# 7segement4digits1badidea-shield-mk-1.net
KiCad netlist of a schematic drawn in EAGLE
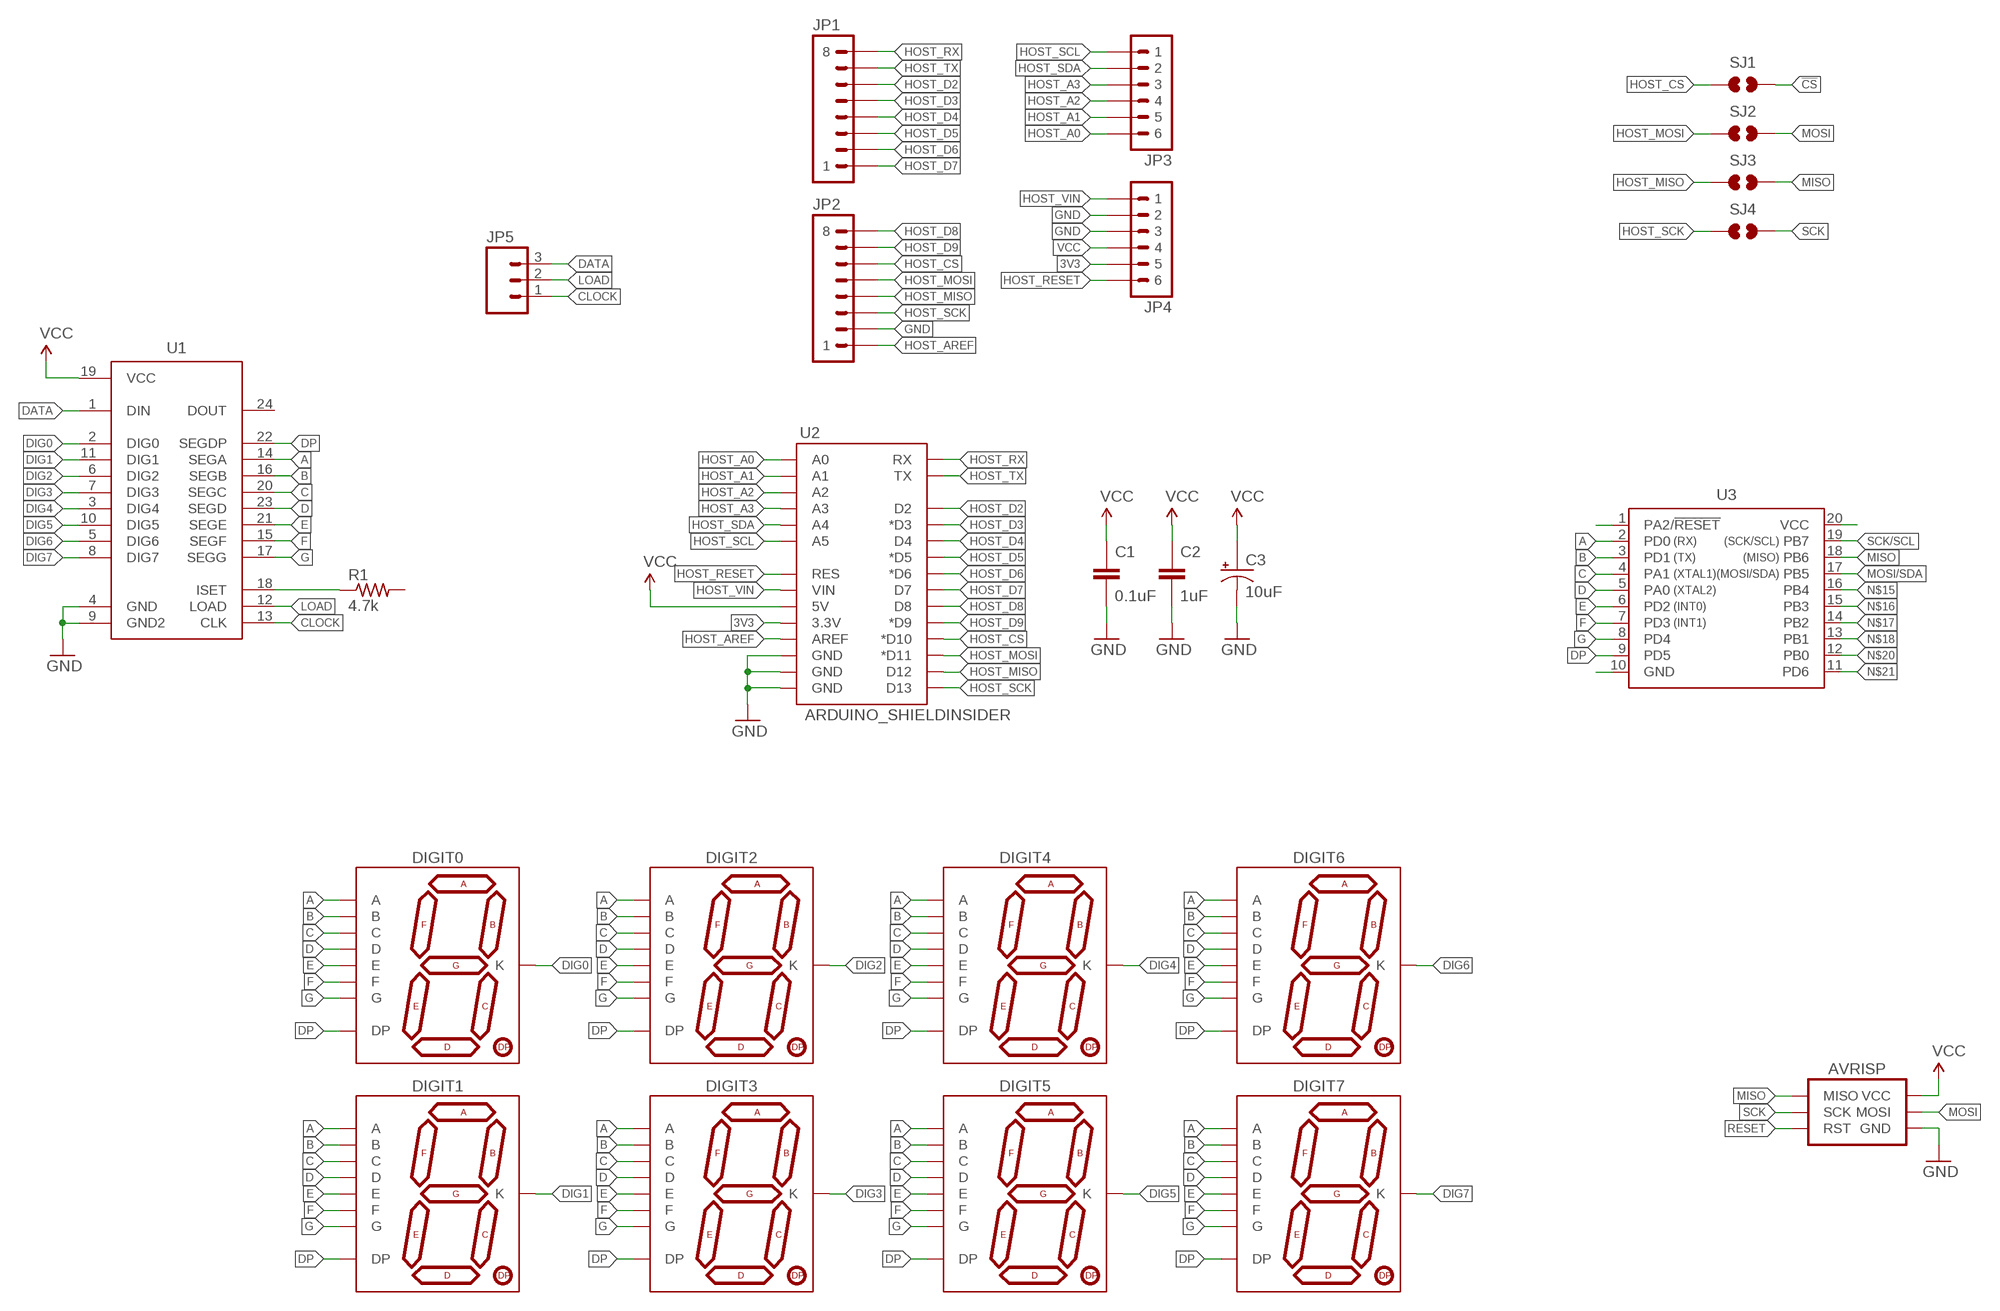
[diagram p0: schematic, sheet 1]

(export (version "E")
  (design (tool "Eeschema 10.0.6"))
  (components
    (comp (ref "AVRISP")
      (value "AVR_SPI_PRG_6PTH")
      (footprint "eagle-import:2X3")
      (libsource (lib "eagle-import") (part "AVR_SPI_PRG_6PTH"))
    )
    (comp (ref "C1")
      (value "0.1uF")
      (footprint "eagle-import:C025-024X044")
      (libsource (lib "eagle-import") (part "CAPACITOR-CERAMIC025-024X044"))
    )
    (comp (ref "C2")
      (value "1uF")
      (footprint "eagle-import:C025-024X044")
      (libsource (lib "eagle-import") (part "CAPACITOR-CERAMIC025-024X044"))
    )
    (comp (ref "C3")
      (value "10uF")
      (footprint "eagle-import:E2,5-5")
      (libsource (lib "eagle-import") (part "CAPACITOR-POLARIZEDE2.5-5"))
    )
    (comp (ref "DIGIT0")
      (value "7SEG_1DIGPTH-10MM")
      (footprint "eagle-import:7SEG_1DIG_10MM")
      (libsource (lib "eagle-import") (part "7SEG_1DIGPTH-10MM"))
    )
    (comp (ref "DIGIT1")
      (value "7SEG_1DIGPTH-10MM")
      (footprint "eagle-import:7SEG_1DIG_10MM")
      (libsource (lib "eagle-import") (part "7SEG_1DIGPTH-10MM"))
    )
    (comp (ref "DIGIT2")
      (value "7SEG_1DIGPTH-10MM")
      (footprint "eagle-import:7SEG_1DIG_10MM")
      (libsource (lib "eagle-import") (part "7SEG_1DIGPTH-10MM"))
    )
    (comp (ref "DIGIT3")
      (value "7SEG_1DIGPTH-10MM")
      (footprint "eagle-import:7SEG_1DIG_10MM")
      (libsource (lib "eagle-import") (part "7SEG_1DIGPTH-10MM"))
    )
    (comp (ref "DIGIT4")
      (value "7SEG_1DIGPTH-10MM")
      (footprint "eagle-import:7SEG_1DIG_10MM")
      (libsource (lib "eagle-import") (part "7SEG_1DIGPTH-10MM"))
    )
    (comp (ref "DIGIT5")
      (value "7SEG_1DIGPTH-10MM")
      (footprint "eagle-import:7SEG_1DIG_10MM")
      (libsource (lib "eagle-import") (part "7SEG_1DIGPTH-10MM"))
    )
    (comp (ref "DIGIT6")
      (value "7SEG_1DIGPTH-10MM")
      (footprint "eagle-import:7SEG_1DIG_10MM")
      (libsource (lib "eagle-import") (part "7SEG_1DIGPTH-10MM"))
    )
    (comp (ref "DIGIT7")
      (value "7SEG_1DIGPTH-10MM")
      (footprint "eagle-import:7SEG_1DIG_10MM")
      (libsource (lib "eagle-import") (part "7SEG_1DIGPTH-10MM"))
    )
    (comp (ref "JP1")
      (value "M081X08")
      (footprint "eagle-import:1X08")
      (libsource (lib "eagle-import") (part "M081X08"))
    )
    (comp (ref "JP2")
      (value "M081X08")
      (footprint "eagle-import:1X08")
      (libsource (lib "eagle-import") (part "M081X08"))
    )
    (comp (ref "JP3")
      (value "M06-NOBS-PTH")
      (footprint "eagle-import:1X06_NOLOCK_FUCKITALL")
      (libsource (lib "eagle-import") (part "M06-NOBS-PTH"))
    )
    (comp (ref "JP4")
      (value "M06-NOBS-PTH")
      (footprint "eagle-import:1X06_NOLOCK_FUCKITALL")
      (libsource (lib "eagle-import") (part "M06-NOBS-PTH"))
    )
    (comp (ref "JP5")
      (value "M03PTH")
      (footprint "eagle-import:1X03")
      (libsource (lib "eagle-import") (part "M03PTH"))
    )
    (comp (ref "R1")
      (value "4.7k")
      (footprint "eagle-import:RESISTOR-AXIAL-PTH-6.35MM")
      (libsource (lib "eagle-import") (part "RESISTORPTH-AXIAL-6.35MM"))
    )
    (comp (ref "SJ1")
      (value "JUMPER-PAD-2-NOYES_SILK")
      (footprint "eagle-import:PAD-JUMPER-2-NO_YES_SILK")
      (libsource (lib "eagle-import") (part "JUMPER-PAD-2-NOYES_SILK"))
    )
    (comp (ref "SJ2")
      (value "JUMPER-PAD-2-NOYES_SILK")
      (footprint "eagle-import:PAD-JUMPER-2-NO_YES_SILK")
      (libsource (lib "eagle-import") (part "JUMPER-PAD-2-NOYES_SILK"))
    )
    (comp (ref "SJ3")
      (value "JUMPER-PAD-2-NOYES_SILK")
      (footprint "eagle-import:PAD-JUMPER-2-NO_YES_SILK")
      (libsource (lib "eagle-import") (part "JUMPER-PAD-2-NOYES_SILK"))
    )
    (comp (ref "SJ4")
      (value "JUMPER-PAD-2-NOYES_SILK")
      (footprint "eagle-import:PAD-JUMPER-2-NO_YES_SILK")
      (libsource (lib "eagle-import") (part "JUMPER-PAD-2-NOYES_SILK"))
    )
    (comp (ref "U1")
      (value "MAX7219DIP")
      (footprint "eagle-import:DIL24")
      (libsource (lib "eagle-import") (part "MAX7219DIP"))
    )
    (comp (ref "U2")
      (value "ARDUINO_SHIELDINSIDER")
      (footprint "eagle-import:ARDUINO_SHIELD_NOOUTLINE_INSIDE")
      (libsource (lib "eagle-import") (part "ARDUINO_SHIELDINSIDER"))
    )
    (comp (ref "U3")
      (value "ATTINY2313ADIP")
      (footprint "eagle-import:DIL20")
      (libsource (lib "eagle-import") (part "ATTINY2313ADIP"))
    )
  )
  (nets
    (net (code "1") (name "/~{CS}") (class "Default")
      (node (ref "SJ1") (pin "2") (pinfunction "2_2") (pintype "passive"))
    )
    (net (code "2") (name "3V3") (class "Default")
      (node (ref "JP4") (pin "5") (pinfunction "5_5") (pintype "passive"))
      (node (ref "U2") (pin "3.3V") (pinfunction "3.3V_3.3V") (pintype "bidirectional"))
    )
    (net (code "3") (name "A") (class "Default")
      (node (ref "DIGIT0") (pin "10") (pinfunction "A_10") (pintype "bidirectional"))
      (node (ref "DIGIT1") (pin "10") (pinfunction "A_10") (pintype "bidirectional"))
      (node (ref "DIGIT2") (pin "10") (pinfunction "A_10") (pintype "bidirectional"))
      (node (ref "DIGIT3") (pin "10") (pinfunction "A_10") (pintype "bidirectional"))
      (node (ref "DIGIT4") (pin "10") (pinfunction "A_10") (pintype "bidirectional"))
      (node (ref "DIGIT5") (pin "10") (pinfunction "A_10") (pintype "bidirectional"))
      (node (ref "DIGIT6") (pin "10") (pinfunction "A_10") (pintype "bidirectional"))
      (node (ref "DIGIT7") (pin "10") (pinfunction "A_10") (pintype "bidirectional"))
      (node (ref "U1") (pin "14") (pinfunction "SEGA_14") (pintype "bidirectional"))
      (node (ref "U3") (pin "2") (pinfunction "PD0_2") (pintype "bidirectional"))
    )
    (net (code "4") (name "B") (class "Default")
      (node (ref "DIGIT0") (pin "9") (pinfunction "B_9") (pintype "bidirectional"))
      (node (ref "DIGIT1") (pin "9") (pinfunction "B_9") (pintype "bidirectional"))
      (node (ref "DIGIT2") (pin "9") (pinfunction "B_9") (pintype "bidirectional"))
      (node (ref "DIGIT3") (pin "9") (pinfunction "B_9") (pintype "bidirectional"))
      (node (ref "DIGIT4") (pin "9") (pinfunction "B_9") (pintype "bidirectional"))
      (node (ref "DIGIT5") (pin "9") (pinfunction "B_9") (pintype "bidirectional"))
      (node (ref "DIGIT6") (pin "9") (pinfunction "B_9") (pintype "bidirectional"))
      (node (ref "DIGIT7") (pin "9") (pinfunction "B_9") (pintype "bidirectional"))
      (node (ref "U1") (pin "16") (pinfunction "SEGB_16") (pintype "bidirectional"))
      (node (ref "U3") (pin "3") (pinfunction "PD1_3") (pintype "bidirectional"))
    )
    (net (code "5") (name "C") (class "Default")
      (node (ref "DIGIT0") (pin "8") (pinfunction "C_8") (pintype "bidirectional"))
      (node (ref "DIGIT1") (pin "8") (pinfunction "C_8") (pintype "bidirectional"))
      (node (ref "DIGIT2") (pin "8") (pinfunction "C_8") (pintype "bidirectional"))
      (node (ref "DIGIT3") (pin "8") (pinfunction "C_8") (pintype "bidirectional"))
      (node (ref "DIGIT4") (pin "8") (pinfunction "C_8") (pintype "bidirectional"))
      (node (ref "DIGIT5") (pin "8") (pinfunction "C_8") (pintype "bidirectional"))
      (node (ref "DIGIT6") (pin "8") (pinfunction "C_8") (pintype "bidirectional"))
      (node (ref "DIGIT7") (pin "8") (pinfunction "C_8") (pintype "bidirectional"))
      (node (ref "U1") (pin "20") (pinfunction "SEGC_20") (pintype "bidirectional"))
      (node (ref "U3") (pin "4") (pinfunction "PA1_4") (pintype "bidirectional"))
    )
    (net (code "6") (name "CLOCK") (class "Default")
      (node (ref "JP5") (pin "1") (pinfunction "1_1") (pintype "passive"))
      (node (ref "U1") (pin "13") (pinfunction "CLK_13") (pintype "bidirectional"))
    )
    (net (code "7") (name "D") (class "Default")
      (node (ref "DIGIT0") (pin "5") (pinfunction "D_5") (pintype "bidirectional"))
      (node (ref "DIGIT1") (pin "5") (pinfunction "D_5") (pintype "bidirectional"))
      (node (ref "DIGIT2") (pin "5") (pinfunction "D_5") (pintype "bidirectional"))
      (node (ref "DIGIT3") (pin "5") (pinfunction "D_5") (pintype "bidirectional"))
      (node (ref "DIGIT4") (pin "5") (pinfunction "D_5") (pintype "bidirectional"))
      (node (ref "DIGIT5") (pin "5") (pinfunction "D_5") (pintype "bidirectional"))
      (node (ref "DIGIT6") (pin "5") (pinfunction "D_5") (pintype "bidirectional"))
      (node (ref "DIGIT7") (pin "5") (pinfunction "D_5") (pintype "bidirectional"))
      (node (ref "U1") (pin "23") (pinfunction "SEGD_23") (pintype "bidirectional"))
      (node (ref "U3") (pin "5") (pinfunction "PA0_5") (pintype "bidirectional"))
    )
    (net (code "8") (name "DATA") (class "Default")
      (node (ref "JP5") (pin "3") (pinfunction "3_3") (pintype "passive"))
      (node (ref "U1") (pin "1") (pinfunction "DIN_1") (pintype "bidirectional"))
    )
    (net (code "9") (name "DIG0") (class "Default")
      (node (ref "DIGIT0") (pin "1") (pinfunction "K_1") (pintype "bidirectional"))
      (node (ref "DIGIT0") (pin "6") (pinfunction "K_6") (pintype "bidirectional"))
      (node (ref "U1") (pin "2") (pinfunction "DIG0_2") (pintype "bidirectional"))
    )
    (net (code "10") (name "DIG1") (class "Default")
      (node (ref "DIGIT1") (pin "1") (pinfunction "K_1") (pintype "bidirectional"))
      (node (ref "DIGIT1") (pin "6") (pinfunction "K_6") (pintype "bidirectional"))
      (node (ref "U1") (pin "11") (pinfunction "DIG1_11") (pintype "bidirectional"))
    )
    (net (code "11") (name "DIG2") (class "Default")
      (node (ref "DIGIT2") (pin "1") (pinfunction "K_1") (pintype "bidirectional"))
      (node (ref "DIGIT2") (pin "6") (pinfunction "K_6") (pintype "bidirectional"))
      (node (ref "U1") (pin "6") (pinfunction "DIG2_6") (pintype "bidirectional"))
    )
    (net (code "12") (name "DIG3") (class "Default")
      (node (ref "DIGIT3") (pin "1") (pinfunction "K_1") (pintype "bidirectional"))
      (node (ref "DIGIT3") (pin "6") (pinfunction "K_6") (pintype "bidirectional"))
      (node (ref "U1") (pin "7") (pinfunction "DIG3_7") (pintype "bidirectional"))
    )
    (net (code "13") (name "DIG4") (class "Default")
      (node (ref "DIGIT4") (pin "1") (pinfunction "K_1") (pintype "bidirectional"))
      (node (ref "DIGIT4") (pin "6") (pinfunction "K_6") (pintype "bidirectional"))
      (node (ref "U1") (pin "3") (pinfunction "DIG4_3") (pintype "bidirectional"))
    )
    (net (code "14") (name "DIG5") (class "Default")
      (node (ref "DIGIT5") (pin "1") (pinfunction "K_1") (pintype "bidirectional"))
      (node (ref "DIGIT5") (pin "6") (pinfunction "K_6") (pintype "bidirectional"))
      (node (ref "U1") (pin "10") (pinfunction "DIG5_10") (pintype "bidirectional"))
    )
    (net (code "15") (name "DIG6") (class "Default")
      (node (ref "DIGIT6") (pin "1") (pinfunction "K_1") (pintype "bidirectional"))
      (node (ref "DIGIT6") (pin "6") (pinfunction "K_6") (pintype "bidirectional"))
      (node (ref "U1") (pin "5") (pinfunction "DIG6_5") (pintype "bidirectional"))
    )
    (net (code "16") (name "DIG7") (class "Default")
      (node (ref "DIGIT7") (pin "1") (pinfunction "K_1") (pintype "bidirectional"))
      (node (ref "DIGIT7") (pin "6") (pinfunction "K_6") (pintype "bidirectional"))
      (node (ref "U1") (pin "8") (pinfunction "DIG7_8") (pintype "bidirectional"))
    )
    (net (code "17") (name "DP") (class "Default")
      (node (ref "DIGIT0") (pin "7") (pinfunction "DP_7") (pintype "bidirectional"))
      (node (ref "DIGIT1") (pin "7") (pinfunction "DP_7") (pintype "bidirectional"))
      (node (ref "DIGIT2") (pin "7") (pinfunction "DP_7") (pintype "bidirectional"))
      (node (ref "DIGIT3") (pin "7") (pinfunction "DP_7") (pintype "bidirectional"))
      (node (ref "DIGIT4") (pin "7") (pinfunction "DP_7") (pintype "bidirectional"))
      (node (ref "DIGIT5") (pin "7") (pinfunction "DP_7") (pintype "bidirectional"))
      (node (ref "DIGIT6") (pin "7") (pinfunction "DP_7") (pintype "bidirectional"))
      (node (ref "DIGIT7") (pin "7") (pinfunction "DP_7") (pintype "bidirectional"))
      (node (ref "U1") (pin "22") (pinfunction "SEGDP_22") (pintype "bidirectional"))
      (node (ref "U3") (pin "9") (pinfunction "PD5_9") (pintype "bidirectional"))
    )
    (net (code "18") (name "E") (class "Default")
      (node (ref "DIGIT0") (pin "4") (pinfunction "E_4") (pintype "bidirectional"))
      (node (ref "DIGIT1") (pin "4") (pinfunction "E_4") (pintype "bidirectional"))
      (node (ref "DIGIT2") (pin "4") (pinfunction "E_4") (pintype "bidirectional"))
      (node (ref "DIGIT3") (pin "4") (pinfunction "E_4") (pintype "bidirectional"))
      (node (ref "DIGIT4") (pin "4") (pinfunction "E_4") (pintype "bidirectional"))
      (node (ref "DIGIT5") (pin "4") (pinfunction "E_4") (pintype "bidirectional"))
      (node (ref "DIGIT6") (pin "4") (pinfunction "E_4") (pintype "bidirectional"))
      (node (ref "DIGIT7") (pin "4") (pinfunction "E_4") (pintype "bidirectional"))
      (node (ref "U1") (pin "21") (pinfunction "SEGE_21") (pintype "bidirectional"))
      (node (ref "U3") (pin "6") (pinfunction "PD2_6") (pintype "bidirectional"))
    )
    (net (code "19") (name "F") (class "Default")
      (node (ref "DIGIT0") (pin "2") (pinfunction "F_2") (pintype "bidirectional"))
      (node (ref "DIGIT1") (pin "2") (pinfunction "F_2") (pintype "bidirectional"))
      (node (ref "DIGIT2") (pin "2") (pinfunction "F_2") (pintype "bidirectional"))
      (node (ref "DIGIT3") (pin "2") (pinfunction "F_2") (pintype "bidirectional"))
      (node (ref "DIGIT4") (pin "2") (pinfunction "F_2") (pintype "bidirectional"))
      (node (ref "DIGIT5") (pin "2") (pinfunction "F_2") (pintype "bidirectional"))
      (node (ref "DIGIT6") (pin "2") (pinfunction "F_2") (pintype "bidirectional"))
      (node (ref "DIGIT7") (pin "2") (pinfunction "F_2") (pintype "bidirectional"))
      (node (ref "U1") (pin "15") (pinfunction "SEGF_15") (pintype "bidirectional"))
      (node (ref "U3") (pin "7") (pinfunction "PD3_7") (pintype "bidirectional"))
    )
    (net (code "20") (name "G") (class "Default")
      (node (ref "DIGIT0") (pin "3") (pinfunction "G_3") (pintype "bidirectional"))
      (node (ref "DIGIT1") (pin "3") (pinfunction "G_3") (pintype "bidirectional"))
      (node (ref "DIGIT2") (pin "3") (pinfunction "G_3") (pintype "bidirectional"))
      (node (ref "DIGIT3") (pin "3") (pinfunction "G_3") (pintype "bidirectional"))
      (node (ref "DIGIT4") (pin "3") (pinfunction "G_3") (pintype "bidirectional"))
      (node (ref "DIGIT5") (pin "3") (pinfunction "G_3") (pintype "bidirectional"))
      (node (ref "DIGIT6") (pin "3") (pinfunction "G_3") (pintype "bidirectional"))
      (node (ref "DIGIT7") (pin "3") (pinfunction "G_3") (pintype "bidirectional"))
      (node (ref "U1") (pin "17") (pinfunction "SEGG_17") (pintype "bidirectional"))
      (node (ref "U3") (pin "8") (pinfunction "PD4_8") (pintype "bidirectional"))
    )
    (net (code "21") (name "GND") (class "Default")
      (node (ref "AVRISP") (pin "6") (pinfunction "GND_6") (pintype "passive"))
      (node (ref "C1") (pin "2") (pinfunction "2_2") (pintype "passive"))
      (node (ref "C2") (pin "2") (pinfunction "2_2") (pintype "passive"))
      (node (ref "C3") (pin "-") (pinfunction "-_-") (pintype "passive"))
      (node (ref "JP2") (pin "2") (pinfunction "2_2") (pintype "passive"))
      (node (ref "JP4") (pin "2") (pinfunction "2_2") (pintype "passive"))
      (node (ref "JP4") (pin "3") (pinfunction "3_3") (pintype "passive"))
      (node (ref "U1") (pin "4") (pinfunction "GND_4") (pintype "bidirectional"))
      (node (ref "U1") (pin "9") (pinfunction "GND2_9") (pintype "bidirectional"))
      (node (ref "U2") (pin "GND@0") (pinfunction "GND_GND@0") (pintype "bidirectional"))
      (node (ref "U2") (pin "GND@1") (pinfunction "GND_GND@1") (pintype "bidirectional"))
      (node (ref "U2") (pin "GND@2") (pinfunction "GND_GND@2") (pintype "bidirectional"))
    )
    (net (code "22") (name "HOST_A0") (class "Default")
      (node (ref "JP3") (pin "6") (pinfunction "6_6") (pintype "passive"))
      (node (ref "U2") (pin "A0") (pinfunction "A0_A0") (pintype "bidirectional"))
    )
    (net (code "23") (name "HOST_A1") (class "Default")
      (node (ref "JP3") (pin "5") (pinfunction "5_5") (pintype "passive"))
      (node (ref "U2") (pin "A1") (pinfunction "A1_A1") (pintype "bidirectional"))
    )
    (net (code "24") (name "HOST_A2") (class "Default")
      (node (ref "JP3") (pin "4") (pinfunction "4_4") (pintype "passive"))
      (node (ref "U2") (pin "A2") (pinfunction "A2_A2") (pintype "bidirectional"))
    )
    (net (code "25") (name "HOST_A3") (class "Default")
      (node (ref "JP3") (pin "3") (pinfunction "3_3") (pintype "passive"))
      (node (ref "U2") (pin "A3") (pinfunction "A3_A3") (pintype "bidirectional"))
    )
    (net (code "26") (name "HOST_AREF") (class "Default")
      (node (ref "JP2") (pin "1") (pinfunction "1_1") (pintype "passive"))
      (node (ref "U2") (pin "AREF") (pinfunction "AREF_AREF") (pintype "bidirectional"))
    )
    (net (code "27") (name "HOST_CS") (class "Default")
      (node (ref "JP2") (pin "6") (pinfunction "6_6") (pintype "passive"))
      (node (ref "SJ1") (pin "1") (pinfunction "1_1") (pintype "passive"))
      (node (ref "U2") (pin "D10") (pinfunction "*D10_D10") (pintype "bidirectional"))
    )
    (net (code "28") (name "HOST_D2") (class "Default")
      (node (ref "JP1") (pin "6") (pinfunction "6_6") (pintype "passive"))
      (node (ref "U2") (pin "D2") (pinfunction "D2_D2") (pintype "bidirectional"))
    )
    (net (code "29") (name "HOST_D3") (class "Default")
      (node (ref "JP1") (pin "5") (pinfunction "5_5") (pintype "passive"))
      (node (ref "U2") (pin "D3") (pinfunction "*D3_D3") (pintype "bidirectional"))
    )
    (net (code "30") (name "HOST_D4") (class "Default")
      (node (ref "JP1") (pin "4") (pinfunction "4_4") (pintype "passive"))
      (node (ref "U2") (pin "D4") (pinfunction "D4_D4") (pintype "bidirectional"))
    )
    (net (code "31") (name "HOST_D5") (class "Default")
      (node (ref "JP1") (pin "3") (pinfunction "3_3") (pintype "passive"))
      (node (ref "U2") (pin "D5") (pinfunction "*D5_D5") (pintype "bidirectional"))
    )
    (net (code "32") (name "HOST_D6") (class "Default")
      (node (ref "JP1") (pin "2") (pinfunction "2_2") (pintype "passive"))
      (node (ref "U2") (pin "D6") (pinfunction "*D6_D6") (pintype "bidirectional"))
    )
    (net (code "33") (name "HOST_D7") (class "Default")
      (node (ref "JP1") (pin "1") (pinfunction "1_1") (pintype "passive"))
      (node (ref "U2") (pin "D7") (pinfunction "D7_D7") (pintype "bidirectional"))
    )
    (net (code "34") (name "HOST_D8") (class "Default")
      (node (ref "JP2") (pin "8") (pinfunction "8_8") (pintype "passive"))
      (node (ref "U2") (pin "D8") (pinfunction "D8_D8") (pintype "bidirectional"))
    )
    (net (code "35") (name "HOST_D9") (class "Default")
      (node (ref "JP2") (pin "7") (pinfunction "7_7") (pintype "passive"))
      (node (ref "U2") (pin "D9") (pinfunction "*D9_D9") (pintype "bidirectional"))
    )
    (net (code "36") (name "HOST_MISO") (class "Default")
      (node (ref "JP2") (pin "4") (pinfunction "4_4") (pintype "passive"))
      (node (ref "SJ3") (pin "1") (pinfunction "1_1") (pintype "passive"))
      (node (ref "U2") (pin "D12") (pinfunction "D12_D12") (pintype "bidirectional"))
    )
    (net (code "37") (name "HOST_MOSI") (class "Default")
      (node (ref "JP2") (pin "5") (pinfunction "5_5") (pintype "passive"))
      (node (ref "SJ2") (pin "1") (pinfunction "1_1") (pintype "passive"))
      (node (ref "U2") (pin "D11") (pinfunction "*D11_D11") (pintype "bidirectional"))
    )
    (net (code "38") (name "HOST_RESET") (class "Default")
      (node (ref "JP4") (pin "6") (pinfunction "6_6") (pintype "passive"))
      (node (ref "U2") (pin "RES") (pinfunction "RES_RES") (pintype "bidirectional"))
    )
    (net (code "39") (name "HOST_RX") (class "Default")
      (node (ref "JP1") (pin "8") (pinfunction "8_8") (pintype "passive"))
      (node (ref "U2") (pin "RX") (pinfunction "RX_RX") (pintype "bidirectional"))
    )
    (net (code "40") (name "HOST_SCK") (class "Default")
      (node (ref "JP2") (pin "3") (pinfunction "3_3") (pintype "passive"))
      (node (ref "SJ4") (pin "1") (pinfunction "1_1") (pintype "passive"))
      (node (ref "U2") (pin "D13") (pinfunction "D13_D13") (pintype "bidirectional"))
    )
    (net (code "41") (name "HOST_SCL") (class "Default")
      (node (ref "JP3") (pin "1") (pinfunction "1_1") (pintype "passive"))
      (node (ref "U2") (pin "A5") (pinfunction "A5_A5") (pintype "bidirectional"))
    )
    (net (code "42") (name "HOST_SDA") (class "Default")
      (node (ref "JP3") (pin "2") (pinfunction "2_2") (pintype "passive"))
      (node (ref "U2") (pin "A4") (pinfunction "A4_A4") (pintype "bidirectional"))
    )
    (net (code "43") (name "HOST_TX") (class "Default")
      (node (ref "JP1") (pin "7") (pinfunction "7_7") (pintype "passive"))
      (node (ref "U2") (pin "TX") (pinfunction "TX_TX") (pintype "bidirectional"))
    )
    (net (code "44") (name "HOST_VIN") (class "Default")
      (node (ref "JP4") (pin "1") (pinfunction "1_1") (pintype "passive"))
      (node (ref "U2") (pin "VIN") (pinfunction "VIN_VIN") (pintype "bidirectional"))
    )
    (net (code "45") (name "LOAD") (class "Default")
      (node (ref "JP5") (pin "2") (pinfunction "2_2") (pintype "passive"))
      (node (ref "U1") (pin "12") (pinfunction "LOAD_12") (pintype "bidirectional"))
    )
    (net (code "46") (name "MISO") (class "Default")
      (node (ref "AVRISP") (pin "1") (pinfunction "MISO_1") (pintype "passive"))
      (node (ref "SJ3") (pin "2") (pinfunction "2_2") (pintype "passive"))
      (node (ref "U3") (pin "18") (pinfunction "PB6_18") (pintype "bidirectional"))
    )
    (net (code "47") (name "MOSI") (class "Default")
      (node (ref "AVRISP") (pin "4") (pinfunction "MOSI_4") (pintype "passive"))
      (node (ref "SJ2") (pin "2") (pinfunction "2_2") (pintype "passive"))
    )
    (net (code "48") (name "MOSI{slash}SDA") (class "Default")
      (node (ref "U3") (pin "17") (pinfunction "PB5_17") (pintype "bidirectional"))
    )
    (net (code "49") (name "N$15") (class "Default")
      (node (ref "U3") (pin "16") (pinfunction "PB4_16") (pintype "bidirectional"))
    )
    (net (code "50") (name "N$16") (class "Default")
      (node (ref "U3") (pin "15") (pinfunction "PB3_15") (pintype "bidirectional"))
    )
    (net (code "51") (name "N$17") (class "Default")
      (node (ref "U3") (pin "14") (pinfunction "PB2_14") (pintype "bidirectional"))
    )
    (net (code "52") (name "N$18") (class "Default")
      (node (ref "U3") (pin "13") (pinfunction "PB1_13") (pintype "bidirectional"))
    )
    (net (code "53") (name "N$20") (class "Default")
      (node (ref "U3") (pin "12") (pinfunction "PB0_12") (pintype "bidirectional"))
    )
    (net (code "54") (name "N$21") (class "Default")
      (node (ref "U3") (pin "11") (pinfunction "PD6_11") (pintype "bidirectional"))
    )
    (net (code "55") (name "Net-(R1-1)") (class "Default")
      (node (ref "R1") (pin "P$1") (pinfunction "1_P$1") (pintype "passive"))
      (node (ref "U1") (pin "18") (pinfunction "ISET_18") (pintype "bidirectional"))
    )
    (net (code "56") (name "RESET") (class "Default")
      (node (ref "AVRISP") (pin "5") (pinfunction "RST_5") (pintype "passive"))
    )
    (net (code "57") (name "SCK") (class "Default")
      (node (ref "AVRISP") (pin "3") (pinfunction "SCK_3") (pintype "passive"))
      (node (ref "SJ4") (pin "2") (pinfunction "2_2") (pintype "passive"))
    )
    (net (code "58") (name "SCK{slash}SCL") (class "Default")
      (node (ref "U3") (pin "19") (pinfunction "PB7_19") (pintype "bidirectional"))
    )
    (net (code "59") (name "VCC") (class "Default")
      (node (ref "AVRISP") (pin "2") (pinfunction "VCC_2") (pintype "passive"))
      (node (ref "C1") (pin "1") (pinfunction "1_1") (pintype "passive"))
      (node (ref "C2") (pin "1") (pinfunction "1_1") (pintype "passive"))
      (node (ref "C3") (pin "+") (pinfunction "+_+") (pintype "passive"))
      (node (ref "JP4") (pin "4") (pinfunction "4_4") (pintype "passive"))
      (node (ref "U1") (pin "19") (pinfunction "VCC_19") (pintype "bidirectional"))
      (node (ref "U2") (pin "5V") (pinfunction "5V_5V") (pintype "bidirectional"))
    )
    (net (code "60") (name "unconnected-(R1-2-PadP$2)") (class "Default")
      (node (ref "R1") (pin "P$2") (pinfunction "2_P$2") (pintype "passive"))
    )
    (net (code "61") (name "unconnected-(U1-DOUT-Pad24)") (class "Default")
      (node (ref "U1") (pin "24") (pinfunction "DOUT_24") (pintype "bidirectional"))
    )
    (net (code "62") (name "unconnected-(U3-GND-Pad10)") (class "Default")
      (node (ref "U3") (pin "10") (pinfunction "GND_10") (pintype "bidirectional"))
    )
    (net (code "63") (name "unconnected-(U3-PA2{slash}~{RESET}-Pad1)") (class "Default")
      (node (ref "U3") (pin "1") (pinfunction "PA2/~{RESET}_1") (pintype "bidirectional"))
    )
    (net (code "64") (name "unconnected-(U3-VCC-Pad20)") (class "Default")
      (node (ref "U3") (pin "20") (pinfunction "VCC_20") (pintype "bidirectional"))
    )
  )
)
